# icst-button.net
KiCad netlist of a schematic drawn in EAGLE
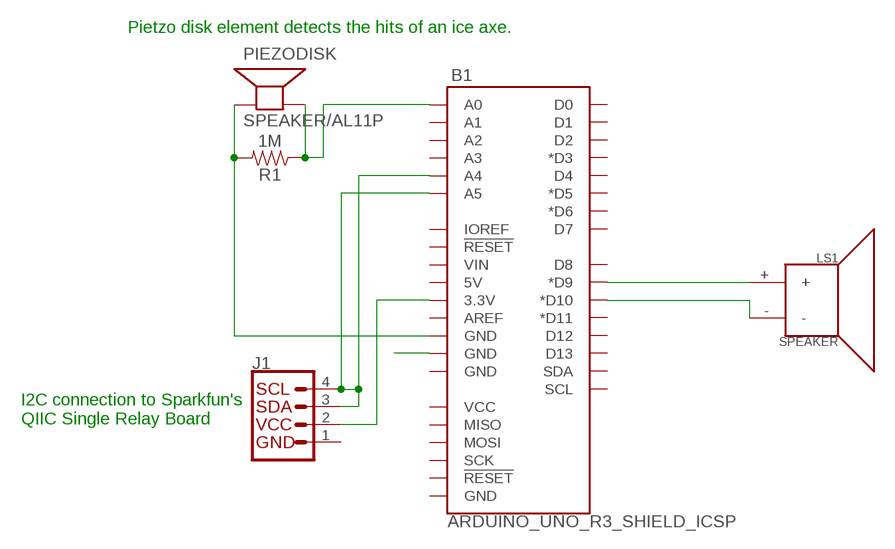
[diagram p0: schematic, sheet 1]

(export (version "E")
  (design (tool "Eeschema 10.0.6"))
  (components
    (comp (ref "B1")
      (value "ARDUINO_UNO_R3_SHIELD_ICSP")
      (footprint "eagle-import:UNO_R3_SHIELD_ICSP")
      (libsource (lib "eagle-import") (part "ARDUINO_UNO_R3_SHIELD_ICSP"))
    )
    (comp (ref "J1")
      (value "QWIIC_CONNECTORJS-1MM")
      (footprint "eagle-import:1X04_1MM_RA")
      (libsource (lib "eagle-import") (part "QWIIC_CONNECTORJS-1MM"))
    )
    (comp (ref "LS1")
      (value "SPEAKER")
      (footprint "eagle-import:PCB_MOUNT_SPEAKER")
      (libsource (lib "eagle-import") (part "SPEAKER"))
    )
    (comp (ref "PIEZODISK")
      (value "SPEAKER/AL11P")
      (footprint "eagle-import:AL11P")
      (libsource (lib "eagle-import") (part "SPEAKER/AL11P"))
    )
    (comp (ref "R1")
      (value "1M")
      (footprint "eagle-import:0603")
      (libsource (lib "eagle-import") (part "1MOHM-0603-1/4W-5%"))
    )
  )
  (nets
    (net (code "1") (name "/GND") (class "Default")
      (node (ref "J1") (pin "1") (pinfunction "GND_1") (pintype "power_in"))
    )
    (net (code "2") (name "Net-(B1-*D9)") (class "Default")
      (node (ref "B1") (pin "D9") (pinfunction "*D9_D9") (pintype "bidirectional"))
      (node (ref "LS1") (pin "+") (pinfunction "+_+") (pintype "bidirectional"))
    )
    (net (code "3") (name "Net-(B1-*D10)") (class "Default")
      (node (ref "B1") (pin "D10") (pinfunction "*D10_D10") (pintype "bidirectional"))
      (node (ref "LS1") (pin "-") (pinfunction "-_-") (pintype "bidirectional"))
    )
    (net (code "4") (name "Net-(B1-GND-PadGND@2)") (class "Default")
      (node (ref "B1") (pin "GND@2") (pinfunction "GND_GND@2") (pintype "bidirectional"))
      (node (ref "PIEZODISK") (pin "+") (pinfunction "+_+") (pintype "passive"))
      (node (ref "R1") (pin "2") (pinfunction "2_2") (pintype "passive"))
    )
    (net (code "5") (name "Net-(B1-PadA0)") (class "Default")
      (node (ref "B1") (pin "A0") (pinfunction "A0_A0") (pintype "bidirectional"))
      (node (ref "PIEZODISK") (pin "-") (pinfunction "-_-") (pintype "passive"))
      (node (ref "R1") (pin "1") (pinfunction "1_1") (pintype "passive"))
    )
    (net (code "6") (name "Net-(J1-SCL)") (class "Default")
      (node (ref "B1") (pin "A4") (pinfunction "A4_A4") (pintype "bidirectional"))
      (node (ref "B1") (pin "A5") (pinfunction "A5_A5") (pintype "bidirectional"))
      (node (ref "J1") (pin "3") (pinfunction "SDA_3") (pintype "passive"))
      (node (ref "J1") (pin "4") (pinfunction "SCL_4") (pintype "passive"))
    )
    (net (code "7") (name "Net-(J1-VCC)") (class "Default")
      (node (ref "B1") (pin "3.3V") (pinfunction "3.3V_3.3V") (pintype "bidirectional"))
      (node (ref "J1") (pin "2") (pinfunction "VCC_2") (pintype "power_in"))
    )
    (net (code "8") (name "unconnected-(B1-*D3-PadD3)") (class "Default")
      (node (ref "B1") (pin "D3") (pinfunction "*D3_D3") (pintype "bidirectional"))
    )
    (net (code "9") (name "unconnected-(B1-*D5-PadD5)") (class "Default")
      (node (ref "B1") (pin "D5") (pinfunction "*D5_D5") (pintype "bidirectional"))
    )
    (net (code "10") (name "unconnected-(B1-*D6-PadD6)") (class "Default")
      (node (ref "B1") (pin "D6") (pinfunction "*D6_D6") (pintype "bidirectional"))
    )
    (net (code "11") (name "unconnected-(B1-*D11-PadD11)") (class "Default")
      (node (ref "B1") (pin "D11") (pinfunction "*D11_D11") (pintype "bidirectional"))
    )
    (net (code "12") (name "unconnected-(B1-D0-PadRX)") (class "Default")
      (node (ref "B1") (pin "RX") (pinfunction "D0_RX") (pintype "bidirectional"))
    )
    (net (code "13") (name "unconnected-(B1-D1-PadTX)") (class "Default")
      (node (ref "B1") (pin "TX") (pinfunction "D1_TX") (pintype "bidirectional"))
    )
    (net (code "14") (name "unconnected-(B1-GND-PadGND@0)") (class "Default")
      (node (ref "B1") (pin "GND@0") (pinfunction "GND_GND@0") (pintype "bidirectional"))
    )
    (net (code "15") (name "unconnected-(B1-GND-PadGND@1)") (class "Default")
      (node (ref "B1") (pin "GND@1") (pinfunction "GND_GND@1") (pintype "bidirectional"))
    )
    (net (code "16") (name "unconnected-(B1-GND-PadGND_ICSP)") (class "Default")
      (node (ref "B1") (pin "GND_ICSP") (pinfunction "GND_GND_ICSP") (pintype "bidirectional"))
    )
    (net (code "17") (name "unconnected-(B1-Pad5V)") (class "Default")
      (node (ref "B1") (pin "5V") (pinfunction "5V_5V") (pintype "bidirectional"))
    )
    (net (code "18") (name "unconnected-(B1-PadA1)") (class "Default")
      (node (ref "B1") (pin "A1") (pinfunction "A1_A1") (pintype "bidirectional"))
    )
    (net (code "19") (name "unconnected-(B1-PadA2)") (class "Default")
      (node (ref "B1") (pin "A2") (pinfunction "A2_A2") (pintype "bidirectional"))
    )
    (net (code "20") (name "unconnected-(B1-PadA3)") (class "Default")
      (node (ref "B1") (pin "A3") (pinfunction "A3_A3") (pintype "bidirectional"))
    )
    (net (code "21") (name "unconnected-(B1-PadAREF)") (class "Default")
      (node (ref "B1") (pin "AREF") (pinfunction "AREF_AREF") (pintype "bidirectional"))
    )
    (net (code "22") (name "unconnected-(B1-PadD2)") (class "Default")
      (node (ref "B1") (pin "D2") (pinfunction "D2_D2") (pintype "bidirectional"))
    )
    (net (code "23") (name "unconnected-(B1-PadD4)") (class "Default")
      (node (ref "B1") (pin "D4") (pinfunction "D4_D4") (pintype "bidirectional"))
    )
    (net (code "24") (name "unconnected-(B1-PadD7)") (class "Default")
      (node (ref "B1") (pin "D7") (pinfunction "D7_D7") (pintype "bidirectional"))
    )
    (net (code "25") (name "unconnected-(B1-PadD8)") (class "Default")
      (node (ref "B1") (pin "D8") (pinfunction "D8_D8") (pintype "bidirectional"))
    )
    (net (code "26") (name "unconnected-(B1-PadD12)") (class "Default")
      (node (ref "B1") (pin "D12") (pinfunction "D12_D12") (pintype "bidirectional"))
    )
    (net (code "27") (name "unconnected-(B1-PadD13)") (class "Default")
      (node (ref "B1") (pin "D13") (pinfunction "D13_D13") (pintype "bidirectional"))
    )
    (net (code "28") (name "unconnected-(B1-PadIOREF)") (class "Default")
      (node (ref "B1") (pin "IOREF") (pinfunction "IOREF_IOREF") (pintype "bidirectional"))
    )
    (net (code "29") (name "unconnected-(B1-PadMISO)") (class "Default")
      (node (ref "B1") (pin "MISO") (pinfunction "MISO_MISO") (pintype "bidirectional"))
    )
    (net (code "30") (name "unconnected-(B1-PadMOSI)") (class "Default")
      (node (ref "B1") (pin "MOSI") (pinfunction "MOSI_MOSI") (pintype "bidirectional"))
    )
    (net (code "31") (name "unconnected-(B1-PadSCK)") (class "Default")
      (node (ref "B1") (pin "SCK") (pinfunction "SCK_SCK") (pintype "bidirectional"))
    )
    (net (code "32") (name "unconnected-(B1-PadSCL)") (class "Default")
      (node (ref "B1") (pin "SCL") (pinfunction "SCL_SCL") (pintype "bidirectional"))
    )
    (net (code "33") (name "unconnected-(B1-PadSDA)") (class "Default")
      (node (ref "B1") (pin "SDA") (pinfunction "SDA_SDA") (pintype "bidirectional"))
    )
    (net (code "34") (name "unconnected-(B1-PadVIN)") (class "Default")
      (node (ref "B1") (pin "VIN") (pinfunction "VIN_VIN") (pintype "bidirectional"))
    )
    (net (code "35") (name "unconnected-(B1-VCC-Pad5V_ICSP)") (class "Default")
      (node (ref "B1") (pin "5V_ICSP") (pinfunction "VCC_5V_ICSP") (pintype "bidirectional"))
    )
    (net (code "36") (name "unconnected-(B1-~{RESET}-PadRES)") (class "Default")
      (node (ref "B1") (pin "RES") (pinfunction "~{RESET}_RES") (pintype "bidirectional"))
    )
    (net (code "37") (name "unconnected-(B1-~{RESET}-PadRST_ICSP)") (class "Default")
      (node (ref "B1") (pin "RST_ICSP") (pinfunction "~{RESET}_RST_ICSP") (pintype "bidirectional"))
    )
  )
)
